# Bank2_I_O.net
KiCad netlist of a schematic drawn in Altium Designer
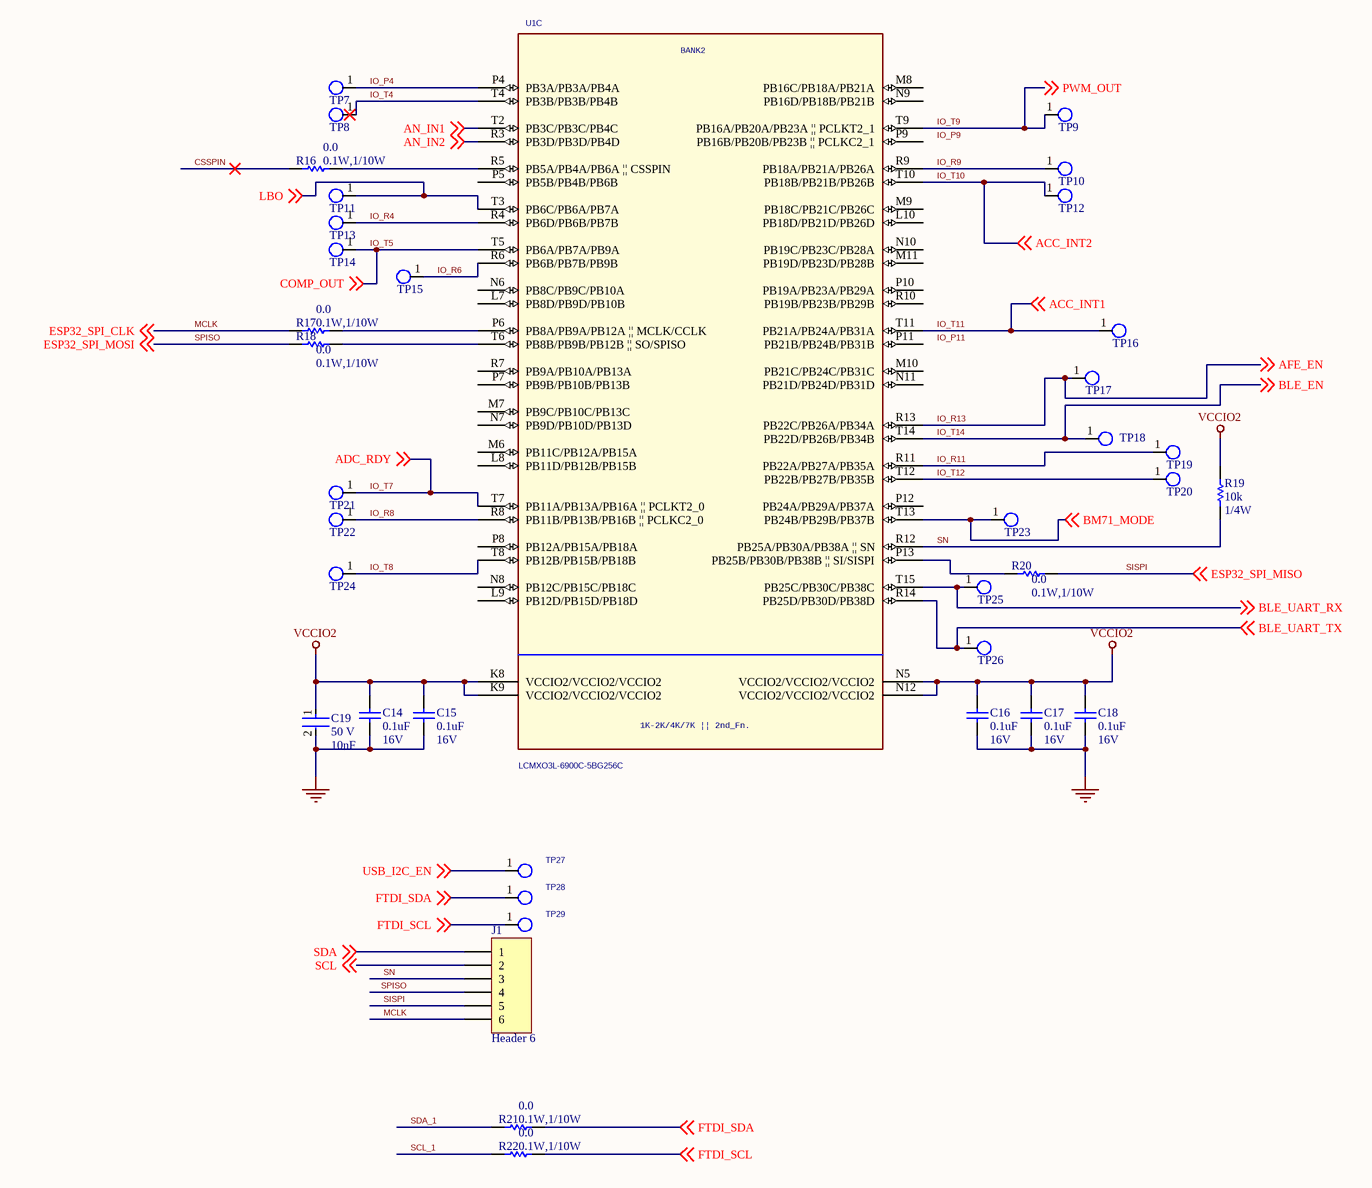
[diagram p0: Bank2_I_O.SchDoc]

(export (version "E")
  (design (tool "Eeschema 10.0.6"))
  (components
    (comp (ref "C14")
      (value "0.1uF")
      (footprint "CAPC1608X87X35ML15T15")
      (description "Ceramic Capacitor 0.1uF 16V +-10% X7R0603")
      (fields
        (field (name "PART NUMBER") "C0603C104M4RACTU")
        (field (name "MANUFACTURER") "Kemet")
        (field (name "VOLTAGE") "16V")
      )
      (libsource (lib "Altium Content Vault") (part "CAP"))
    )
    (comp (ref "C15")
      (value "0.1uF")
      (footprint "CAPC1608X87X35ML15T15")
      (description "Ceramic Capacitor 0.1uF 16V +-10% X7R0603")
      (fields
        (field (name "PART NUMBER") "C0603C104M4RACTU")
        (field (name "MANUFACTURER") "Kemet")
        (field (name "VOLTAGE") "16V")
      )
      (libsource (lib "Altium Content Vault") (part "CAP"))
    )
    (comp (ref "C16")
      (value "0.1uF")
      (footprint "CAPC1608X87X35ML15T15")
      (description "Ceramic Capacitor 0.1uF 16V +-10% X7R0603")
      (fields
        (field (name "PART NUMBER") "C0603C104M4RACTU")
        (field (name "MANUFACTURER") "Kemet")
        (field (name "VOLTAGE") "16V")
      )
      (libsource (lib "Altium Content Vault") (part "CAP"))
    )
    (comp (ref "C17")
      (value "0.1uF")
      (footprint "CAPC1608X87X35ML15T15")
      (description "Ceramic Capacitor 0.1uF 16V +-10% X7R0603")
      (fields
        (field (name "PART NUMBER") "C0603C104M4RACTU")
        (field (name "MANUFACTURER") "Kemet")
        (field (name "VOLTAGE") "16V")
      )
      (libsource (lib "Altium Content Vault") (part "CAP"))
    )
    (comp (ref "C18")
      (value "0.1uF")
      (footprint "CAPC1608X87X35ML15T15")
      (description "Ceramic Capacitor 0.1uF 16V +-10% X7R0603")
      (fields
        (field (name "PART NUMBER") "C0603C104M4RACTU")
        (field (name "MANUFACTURER") "Kemet")
        (field (name "VOLTAGE") "16V")
      )
      (libsource (lib "Altium Content Vault") (part "CAP"))
    )
    (comp (ref "C19")
      (value "10nF")
      (footprint "FP-C0805C-DN-MFG")
      (description "CAP CER 10000PF 50V X7R 0805")
      (fields
        (field (name "VOLTAGE") "50 V")
        (field (name "PART NUMBER") "C0805C103K5RACAUTO")
        (field (name "MANUFACTURER") "KEMET")
      )
      (libsource (lib "Altium Content Vault") (part "b4654b650e69147ec39a6b967a45e02"))
    )
    (comp (ref "J1")
      (value "Header 6")
      (footprint "HDR1X6")
      (description "Header, 6-Pin")
      (fields (field (name "PUBLISHER") "Altium Limited"))
      (libsource (lib "Miscellaneous Connectors") (part "Header 6"))
    )
    (comp (ref "R16")
      (value "0.0")
      (footprint "RESC1608X55X35LL10T10")
      (description "Chip Resistor, 0 Ohm, +/- 5%, 0.1 W, -55 to 155 degC, 0603 (1608 Metric), RoHS, Tape and Reel")
      (fields
        (field (name "POWER") "0.1W,1/10W")
        (field (name "MANUFACTURER") "Samsung-Electro-Mechanics-America,-Inc.")
        (field (name "TOLERANCE") "Jumper")
      )
      (libsource (lib "Altium Content Vault") (part "RES-2"))
    )
    (comp (ref "R17")
      (value "0.0")
      (footprint "RESC1608X55X35LL10T10")
      (description "Chip Resistor, 0 Ohm, +/- 5%, 0.1 W, -55 to 155 degC, 0603 (1608 Metric), RoHS, Tape and Reel")
      (fields
        (field (name "POWER") "0.1W,1/10W")
        (field (name "MANUFACTURER") "Samsung-Electro-Mechanics-America,-Inc.")
        (field (name "TOLERANCE") "Jumper")
      )
      (libsource (lib "Altium Content Vault") (part "RES-2"))
    )
    (comp (ref "R18")
      (value "0.0")
      (footprint "RESC1608X55X35LL10T10")
      (description "Chip Resistor, 0 Ohm, +/- 5%, 0.1 W, -55 to 155 degC, 0603 (1608 Metric), RoHS, Tape and Reel")
      (fields
        (field (name "POWER") "0.1W,1/10W")
        (field (name "MANUFACTURER") "Samsung-Electro-Mechanics-America,-Inc.")
        (field (name "TOLERANCE") "Jumper")
      )
      (libsource (lib "Altium Content Vault") (part "RES-2"))
    )
    (comp (ref "R19")
      (value "10k")
      (footprint "RESC3216X70X50NL05T20")
      (description "Res Thick Film 1206 10k Ohms 5% 1/4W")
      (fields
        (field (name "PART NUMBER") "ERJ-8GEYJ103V")
        (field (name "MANUFACTURER") "Panasonic")
        (field (name "POWER") "1/4W")
      )
      (libsource (lib "Altium Content Vault") (part "RES"))
    )
    (comp (ref "R20")
      (value "0.0")
      (footprint "RESC1608X55X35LL10T10")
      (description "Chip Resistor, 0 Ohm, +/- 5%, 0.1 W, -55 to 155 degC, 0603 (1608 Metric), RoHS, Tape and Reel")
      (fields
        (field (name "POWER") "0.1W,1/10W")
        (field (name "MANUFACTURER") "Samsung-Electro-Mechanics-America,-Inc.")
        (field (name "TOLERANCE") "Jumper")
      )
      (libsource (lib "Altium Content Vault") (part "RES-2"))
    )
    (comp (ref "R21")
      (value "0.0")
      (footprint "RESC1608X55X35LL10T10")
      (description "Chip Resistor, 0 Ohm, +/- 5%, 0.1 W, -55 to 155 degC, 0603 (1608 Metric), RoHS, Tape and Reel")
      (fields
        (field (name "POWER") "0.1W,1/10W")
        (field (name "MANUFACTURER") "Samsung-Electro-Mechanics-America,-Inc.")
        (field (name "TOLERANCE") "Jumper")
      )
      (libsource (lib "Altium Content Vault") (part "RES-2"))
    )
    (comp (ref "R22")
      (value "0.0")
      (footprint "RESC1608X55X35LL10T10")
      (description "Chip Resistor, 0 Ohm, +/- 5%, 0.1 W, -55 to 155 degC, 0603 (1608 Metric), RoHS, Tape and Reel")
      (fields
        (field (name "POWER") "0.1W,1/10W")
        (field (name "MANUFACTURER") "Samsung-Electro-Mechanics-America,-Inc.")
        (field (name "TOLERANCE") "Jumper")
      )
      (libsource (lib "Altium Content Vault") (part "RES-2"))
    )
    (comp (ref "TP7")
      (value "Test_Point_SMD")
      (footprint "Test_Point_SMD")
      (libsource (lib "Edson") (part "Test_Point_SMD"))
    )
    (comp (ref "TP8")
      (value "Test_Point_SMD")
      (footprint "Test_Point_SMD")
      (libsource (lib "Edson") (part "Test_Point_SMD"))
    )
    (comp (ref "TP9")
      (value "Test_Point_SMD")
      (footprint "Test_Point_SMD")
      (libsource (lib "Edson") (part "Test_Point_SMD"))
    )
    (comp (ref "TP10")
      (value "Test_Point_SMD")
      (footprint "Test_Point_SMD")
      (libsource (lib "Edson") (part "Test_Point_SMD"))
    )
    (comp (ref "TP11")
      (value "Test_Point_SMD")
      (footprint "Test_Point_SMD")
      (libsource (lib "Edson") (part "Test_Point_SMD"))
    )
    (comp (ref "TP12")
      (value "Test_Point_SMD")
      (footprint "Test_Point_SMD")
      (libsource (lib "Edson") (part "Test_Point_SMD"))
    )
    (comp (ref "TP13")
      (value "Test_Point_SMD")
      (footprint "Test_Point_SMD")
      (libsource (lib "Edson") (part "Test_Point_SMD"))
    )
    (comp (ref "TP14")
      (value "Test_Point_SMD")
      (footprint "Test_Point_SMD")
      (libsource (lib "Edson") (part "Test_Point_SMD"))
    )
    (comp (ref "TP15")
      (value "Test_Point_SMD")
      (footprint "Test_Point_SMD")
      (libsource (lib "Edson") (part "Test_Point_SMD"))
    )
    (comp (ref "TP16")
      (value "Test_Point_SMD")
      (footprint "Test_Point_SMD")
      (libsource (lib "Edson") (part "Test_Point_SMD"))
    )
    (comp (ref "TP17")
      (value "Test_Point_SMD")
      (footprint "Test_Point_SMD")
      (libsource (lib "Edson") (part "Test_Point_SMD"))
    )
    (comp (ref "TP18")
      (value "Test_Point_SMD")
      (footprint "Test_Point_SMD")
      (libsource (lib "Edson") (part "Test_Point_SMD"))
    )
    (comp (ref "TP19")
      (value "Test_Point_SMD")
      (footprint "Test_Point_SMD")
      (libsource (lib "Edson") (part "Test_Point_SMD"))
    )
    (comp (ref "TP20")
      (value "Test_Point_SMD")
      (footprint "Test_Point_SMD")
      (libsource (lib "Edson") (part "Test_Point_SMD"))
    )
    (comp (ref "TP21")
      (value "Test_Point_SMD")
      (footprint "Test_Point_SMD")
      (libsource (lib "Edson") (part "Test_Point_SMD"))
    )
    (comp (ref "TP22")
      (value "Test_Point_SMD")
      (footprint "Test_Point_SMD")
      (libsource (lib "Edson") (part "Test_Point_SMD"))
    )
    (comp (ref "TP23")
      (value "Test_Point_SMD")
      (footprint "Test_Point_SMD")
      (libsource (lib "Edson") (part "Test_Point_SMD"))
    )
    (comp (ref "TP24")
      (value "Test_Point_SMD")
      (footprint "Test_Point_SMD")
      (libsource (lib "Edson") (part "Test_Point_SMD"))
    )
    (comp (ref "TP25")
      (value "Test_Point_SMD")
      (footprint "Test_Point_SMD")
      (libsource (lib "Edson") (part "Test_Point_SMD"))
    )
    (comp (ref "TP26")
      (value "Test_Point_SMD")
      (footprint "Test_Point_SMD")
      (libsource (lib "Edson") (part "Test_Point_SMD"))
    )
    (comp (ref "TP27")
      (value "tp_s_40_63")
      (footprint "tp_s_40_63")
      (description "Square test point, 40mil inner diameter, 63mil outer diameter")
      (libsource (lib "*") (part "TP_S_40_63"))
    )
    (comp (ref "TP28")
      (value "tp_s_40_63")
      (footprint "tp_s_40_63")
      (description "Square test point, 40mil inner diameter, 63mil outer diameter")
      (libsource (lib "*") (part "TP_S_40_63"))
    )
    (comp (ref "TP29")
      (value "tp_s_40_63")
      (footprint "tp_s_40_63")
      (description "Square test point, 40mil inner diameter, 63mil outer diameter")
      (libsource (lib "*") (part "TP_S_40_63"))
    )
    (comp (ref "U1")
      (value "LCMXO3L-6900C-5BG256C")
      (footprint "BGA256C80P16X16_1400X1400X170")
      (description "IC FPGA 6864LUTS 256BGA")
      (fields (field (name "MANUFACTURER") "Lattice semi"))
      (libsource (lib "*") (part "LCMXO3L-1K/2K/4K/7K-BG256"))
    )
  )
  (nets
    (net (code "1") (name "/CSSPIN") (class "Default")
      (node (ref "R16") (pin "1") (pinfunction "1_1") (pintype "passive"))
    )
    (net (code "2") (name "/IO_P4") (class "Default")
      (node (ref "TP7") (pin "1") (pinfunction "TP_1") (pintype "passive"))
      (node (ref "U1") (pin "P4") (pinfunction "PB3A/PB3A/PB4A_P4") (pintype "bidirectional"))
    )
    (net (code "5") (name "/IO_R4") (class "Default")
      (node (ref "TP13") (pin "1") (pinfunction "TP_1") (pintype "passive"))
      (node (ref "U1") (pin "R4") (pinfunction "PB6D/PB6B/PB7B_R4") (pintype "bidirectional"))
    )
    (net (code "6") (name "/IO_R6") (class "Default")
      (node (ref "TP15") (pin "1") (pinfunction "TP_1") (pintype "passive"))
      (node (ref "U1") (pin "R6") (pinfunction "PB6B/PB7B/PB9B_R6") (pintype "bidirectional"))
    )
    (net (code "7") (name "/IO_R8") (class "Default")
      (node (ref "TP22") (pin "1") (pinfunction "TP_1") (pintype "passive"))
      (node (ref "U1") (pin "R8") (pinfunction "PB11B/PB13B/PB16B_Ζ_PCLKC2_0_R8") (pintype "bidirectional"))
    )
    (net (code "8") (name "/IO_R9") (class "Default")
      (node (ref "TP10") (pin "1") (pinfunction "TP_1") (pintype "passive"))
      (node (ref "U1") (pin "R9") (pinfunction "PB18A/PB21A/PB26A_R9") (pintype "bidirectional"))
    )
    (net (code "9") (name "/IO_R11") (class "Default")
      (node (ref "TP19") (pin "1") (pinfunction "TP_1") (pintype "passive"))
      (node (ref "U1") (pin "R11") (pinfunction "PB22A/PB27A/PB35A_R11") (pintype "bidirectional"))
    )
    (net (code "10") (name "/IO_T4") (class "Default")
      (node (ref "TP8") (pin "1") (pinfunction "TP_1") (pintype "passive"))
      (node (ref "U1") (pin "T4") (pinfunction "PB3B/PB3B/PB4B_T4") (pintype "bidirectional"))
    )
    (net (code "11") (name "/IO_T8") (class "Default")
      (node (ref "TP24") (pin "1") (pinfunction "TP_1") (pintype "passive"))
      (node (ref "U1") (pin "T8") (pinfunction "PB12B/PB15B/PB18B_T8") (pintype "bidirectional"))
    )
    (net (code "12") (name "/IO_T12") (class "Default")
      (node (ref "TP20") (pin "1") (pinfunction "TP_1") (pintype "passive"))
      (node (ref "U1") (pin "T12") (pinfunction "PB22B/PB27B/PB35B_T12") (pintype "bidirectional"))
    )
    (net (code "13") (name "/SCL_1") (class "Default")
      (node (ref "R22") (pin "1") (pinfunction "1_1") (pintype "passive"))
    )
    (net (code "14") (name "/SDA_1") (class "Default")
      (node (ref "R21") (pin "1") (pinfunction "1_1") (pintype "passive"))
    )
    (net (code "15") (name "/SN") (class "Default")
      (node (ref "J1") (pin "3") (pinfunction "3_3") (pintype "passive"))
      (node (ref "R19") (pin "2") (pinfunction "2_2") (pintype "passive"))
      (node (ref "U1") (pin "R12") (pinfunction "PB25A/PB30A/PB38A_Ζ_SN_R12") (pintype "bidirectional"))
    )
    (net (code "16") (name "ACC_INT1") (class "Default")
      (node (ref "TP16") (pin "1") (pinfunction "TP_1") (pintype "passive"))
      (node (ref "U1") (pin "T11") (pinfunction "PB21A/PB24A/PB31A_T11") (pintype "bidirectional"))
    )
    (net (code "17") (name "ACC_INT2") (class "Default")
      (node (ref "TP12") (pin "1") (pinfunction "TP_1") (pintype "passive"))
      (node (ref "U1") (pin "T10") (pinfunction "PB18B/PB21B/PB26B_T10") (pintype "bidirectional"))
    )
    (net (code "18") (name "ADC_RDY") (class "Default")
      (node (ref "TP21") (pin "1") (pinfunction "TP_1") (pintype "passive"))
      (node (ref "U1") (pin "T7") (pinfunction "PB11A/PB13A/PB16A_Ζ_PCLKT2_0_T7") (pintype "bidirectional"))
    )
    (net (code "19") (name "AFE_EN") (class "Default")
      (node (ref "TP17") (pin "1") (pinfunction "TP_1") (pintype "passive"))
      (node (ref "U1") (pin "R13") (pinfunction "PB22C/PB26A/PB34A_R13") (pintype "bidirectional"))
    )
    (net (code "20") (name "AN_IN1") (class "Default")
      (node (ref "U1") (pin "T2") (pinfunction "PB3C/PB3C/PB4C_T2") (pintype "bidirectional"))
    )
    (net (code "21") (name "AN_IN2") (class "Default")
      (node (ref "U1") (pin "R3") (pinfunction "PB3D/PB3D/PB4D_R3") (pintype "bidirectional"))
    )
    (net (code "22") (name "BLE_EN") (class "Default")
      (node (ref "TP18") (pin "1") (pinfunction "TP_1") (pintype "passive"))
      (node (ref "U1") (pin "T14") (pinfunction "PB22D/PB26B/PB34B_T14") (pintype "bidirectional"))
    )
    (net (code "23") (name "BLE_UART_RX") (class "Default")
      (node (ref "TP25") (pin "1") (pinfunction "TP_1") (pintype "passive"))
      (node (ref "U1") (pin "T15") (pinfunction "PB25C/PB30C/PB38C_T15") (pintype "bidirectional"))
    )
    (net (code "24") (name "BLE_UART_TX") (class "Default")
      (node (ref "TP26") (pin "1") (pinfunction "TP_1") (pintype "passive"))
      (node (ref "U1") (pin "R14") (pinfunction "PB25D/PB30D/PB38D_R14") (pintype "bidirectional"))
    )
    (net (code "25") (name "BM71_MODE") (class "Default")
      (node (ref "TP23") (pin "1") (pinfunction "TP_1") (pintype "passive"))
      (node (ref "U1") (pin "T13") (pinfunction "PB24B/PB29B/PB37B_T13") (pintype "bidirectional"))
    )
    (net (code "26") (name "COMP_OUT") (class "Default")
      (node (ref "TP14") (pin "1") (pinfunction "TP_1") (pintype "passive"))
      (node (ref "U1") (pin "T5") (pinfunction "PB6A/PB7A/PB9A_T5") (pintype "bidirectional"))
    )
    (net (code "27") (name "ESP32_SPI_CLK") (class "Default")
      (node (ref "J1") (pin "6") (pinfunction "6_6") (pintype "passive"))
      (node (ref "R17") (pin "1") (pinfunction "1_1") (pintype "passive"))
    )
    (net (code "28") (name "ESP32_SPI_MISO") (class "Default")
      (node (ref "J1") (pin "5") (pinfunction "5_5") (pintype "passive"))
      (node (ref "R20") (pin "2") (pinfunction "2_2") (pintype "passive"))
    )
    (net (code "29") (name "ESP32_SPI_MOSI") (class "Default")
      (node (ref "J1") (pin "4") (pinfunction "4_4") (pintype "passive"))
      (node (ref "R18") (pin "1") (pinfunction "1_1") (pintype "passive"))
    )
    (net (code "30") (name "FTDI_SCL") (class "Default")
      (node (ref "R22") (pin "2") (pinfunction "2_2") (pintype "passive"))
      (node (ref "TP29") (pin "1") (pinfunction "TP_1") (pintype "passive"))
    )
    (net (code "31") (name "FTDI_SDA") (class "Default")
      (node (ref "R21") (pin "2") (pinfunction "2_2") (pintype "passive"))
      (node (ref "TP28") (pin "1") (pinfunction "TP_1") (pintype "passive"))
    )
    (net (code "32") (name "GND") (class "Default")
      (node (ref "C14") (pin "2") (pinfunction "2_2") (pintype "passive"))
      (node (ref "C15") (pin "2") (pinfunction "2_2") (pintype "passive"))
      (node (ref "C16") (pin "2") (pinfunction "2_2") (pintype "passive"))
      (node (ref "C17") (pin "2") (pinfunction "2_2") (pintype "passive"))
      (node (ref "C18") (pin "2") (pinfunction "2_2") (pintype "passive"))
      (node (ref "C19") (pin "2") (pinfunction "2_2") (pintype "passive"))
    )
    (net (code "33") (name "LBO") (class "Default")
      (node (ref "TP11") (pin "1") (pinfunction "TP_1") (pintype "passive"))
      (node (ref "U1") (pin "T3") (pinfunction "PB6C/PB6A/PB7A_T3") (pintype "bidirectional"))
    )
    (net (code "34") (name "Net-(U1C-PB5A{slash}PB4A{slash}PB6A_Ζ_CSSPIN)") (class "Default")
      (node (ref "R16") (pin "2") (pinfunction "2_2") (pintype "passive"))
      (node (ref "U1") (pin "R5") (pinfunction "PB5A/PB4A/PB6A_Ζ_CSSPIN_R5") (pintype "bidirectional"))
    )
    (net (code "35") (name "Net-(U1C-PB8A{slash}PB9A{slash}PB12A_Ζ_MCLK{slash}CCLK)") (class "Default")
      (node (ref "R17") (pin "2") (pinfunction "2_2") (pintype "passive"))
      (node (ref "U1") (pin "P6") (pinfunction "PB8A/PB9A/PB12A_Ζ_MCLK/CCLK_P6") (pintype "bidirectional"))
    )
    (net (code "36") (name "Net-(U1C-PB8B{slash}PB9B{slash}PB12B_Ζ_SO{slash}SPISO)") (class "Default")
      (node (ref "R18") (pin "2") (pinfunction "2_2") (pintype "passive"))
      (node (ref "U1") (pin "T6") (pinfunction "PB8B/PB9B/PB12B_Ζ_SO/SPISO_T6") (pintype "bidirectional"))
    )
    (net (code "37") (name "Net-(U1C-PB25B{slash}PB30B{slash}PB38B_Ζ_SI{slash}SISPI)") (class "Default")
      (node (ref "R20") (pin "1") (pinfunction "1_1") (pintype "passive"))
      (node (ref "U1") (pin "P13") (pinfunction "PB25B/PB30B/PB38B_Ζ_SI/SISPI_P13") (pintype "bidirectional"))
    )
    (net (code "38") (name "PWM_OUT") (class "Default")
      (node (ref "TP9") (pin "1") (pinfunction "TP_1") (pintype "passive"))
      (node (ref "U1") (pin "T9") (pinfunction "PB16A/PB20A/PB23A_Ζ_PCLKT2_1_T9") (pintype "bidirectional"))
    )
    (net (code "39") (name "SCL") (class "Default")
      (node (ref "J1") (pin "2") (pinfunction "2_2") (pintype "passive"))
    )
    (net (code "40") (name "SDA") (class "Default")
      (node (ref "J1") (pin "1") (pinfunction "1_1") (pintype "passive"))
    )
    (net (code "41") (name "USB_I2C_EN") (class "Default")
      (node (ref "TP27") (pin "1") (pinfunction "TP_1") (pintype "passive"))
    )
    (net (code "42") (name "VCCIO2") (class "Default")
      (node (ref "C14") (pin "1") (pinfunction "1_1") (pintype "passive"))
      (node (ref "C15") (pin "1") (pinfunction "1_1") (pintype "passive"))
      (node (ref "C16") (pin "1") (pinfunction "1_1") (pintype "passive"))
      (node (ref "C17") (pin "1") (pinfunction "1_1") (pintype "passive"))
      (node (ref "C18") (pin "1") (pinfunction "1_1") (pintype "passive"))
      (node (ref "C19") (pin "1") (pinfunction "1_1") (pintype "passive"))
      (node (ref "R19") (pin "1") (pinfunction "1_1") (pintype "passive"))
      (node (ref "U1") (pin "K8") (pinfunction "VCCIO2/VCCIO2/VCCIO2_K8") (pintype "power_in"))
      (node (ref "U1") (pin "K9") (pinfunction "VCCIO2/VCCIO2/VCCIO2_K9") (pintype "power_in"))
      (node (ref "U1") (pin "N12") (pinfunction "VCCIO2/VCCIO2/VCCIO2_N12") (pintype "power_in"))
      (node (ref "U1") (pin "N5") (pinfunction "VCCIO2/VCCIO2/VCCIO2_N5") (pintype "power_in"))
    )
    (net (code "43") (name "unconnected-(U1C-PB5B{slash}PB4B{slash}PB6B-PadP5)") (class "Default")
      (node (ref "U1") (pin "P5") (pinfunction "PB5B/PB4B/PB6B_P5") (pintype "bidirectional"))
    )
    (net (code "44") (name "unconnected-(U1C-PB8C{slash}PB9C{slash}PB10A-PadN6)") (class "Default")
      (node (ref "U1") (pin "N6") (pinfunction "PB8C/PB9C/PB10A_N6") (pintype "bidirectional"))
    )
    (net (code "45") (name "unconnected-(U1C-PB8D{slash}PB9D{slash}PB10B-PadL7)") (class "Default")
      (node (ref "U1") (pin "L7") (pinfunction "PB8D/PB9D/PB10B_L7") (pintype "bidirectional"))
    )
    (net (code "46") (name "unconnected-(U1C-PB9A{slash}PB10A{slash}PB13A-PadR7)") (class "Default")
      (node (ref "U1") (pin "R7") (pinfunction "PB9A/PB10A/PB13A_R7") (pintype "bidirectional"))
    )
    (net (code "47") (name "unconnected-(U1C-PB9B{slash}PB10B{slash}PB13B-PadP7)") (class "Default")
      (node (ref "U1") (pin "P7") (pinfunction "PB9B/PB10B/PB13B_P7") (pintype "bidirectional"))
    )
    (net (code "48") (name "unconnected-(U1C-PB9C{slash}PB10C{slash}PB13C-PadM7)") (class "Default")
      (node (ref "U1") (pin "M7") (pinfunction "PB9C/PB10C/PB13C_M7") (pintype "bidirectional"))
    )
    (net (code "49") (name "unconnected-(U1C-PB9D{slash}PB10D{slash}PB13D-PadN7)") (class "Default")
      (node (ref "U1") (pin "N7") (pinfunction "PB9D/PB10D/PB13D_N7") (pintype "bidirectional"))
    )
    (net (code "50") (name "unconnected-(U1C-PB11C{slash}PB12A{slash}PB15A-PadM6)") (class "Default")
      (node (ref "U1") (pin "M6") (pinfunction "PB11C/PB12A/PB15A_M6") (pintype "bidirectional"))
    )
    (net (code "51") (name "unconnected-(U1C-PB11D{slash}PB12B{slash}PB15B-PadL8)") (class "Default")
      (node (ref "U1") (pin "L8") (pinfunction "PB11D/PB12B/PB15B_L8") (pintype "bidirectional"))
    )
    (net (code "52") (name "unconnected-(U1C-PB12A{slash}PB15A{slash}PB18A-PadP8)") (class "Default")
      (node (ref "U1") (pin "P8") (pinfunction "PB12A/PB15A/PB18A_P8") (pintype "bidirectional"))
    )
    (net (code "53") (name "unconnected-(U1C-PB12C{slash}PB15C{slash}PB18C-PadN8)") (class "Default")
      (node (ref "U1") (pin "N8") (pinfunction "PB12C/PB15C/PB18C_N8") (pintype "bidirectional"))
    )
    (net (code "54") (name "unconnected-(U1C-PB12D{slash}PB15D{slash}PB18D-PadL9)") (class "Default")
      (node (ref "U1") (pin "L9") (pinfunction "PB12D/PB15D/PB18D_L9") (pintype "bidirectional"))
    )
    (net (code "55") (name "unconnected-(U1C-PB16B{slash}PB20B{slash}PB23B_Ζ_PCLKC2_1-PadP9)") (class "Default")
      (node (ref "U1") (pin "P9") (pinfunction "PB16B/PB20B/PB23B_Ζ_PCLKC2_1_P9") (pintype "bidirectional"))
    )
    (net (code "56") (name "unconnected-(U1C-PB16C{slash}PB18A{slash}PB21A-PadM8)") (class "Default")
      (node (ref "U1") (pin "M8") (pinfunction "PB16C/PB18A/PB21A_M8") (pintype "bidirectional"))
    )
    (net (code "57") (name "unconnected-(U1C-PB16D{slash}PB18B{slash}PB21B-PadN9)") (class "Default")
      (node (ref "U1") (pin "N9") (pinfunction "PB16D/PB18B/PB21B_N9") (pintype "bidirectional"))
    )
    (net (code "58") (name "unconnected-(U1C-PB18C{slash}PB21C{slash}PB26C-PadM9)") (class "Default")
      (node (ref "U1") (pin "M9") (pinfunction "PB18C/PB21C/PB26C_M9") (pintype "bidirectional"))
    )
    (net (code "59") (name "unconnected-(U1C-PB18D{slash}PB21D{slash}PB26D-PadL10)") (class "Default")
      (node (ref "U1") (pin "L10") (pinfunction "PB18D/PB21D/PB26D_L10") (pintype "bidirectional"))
    )
    (net (code "60") (name "unconnected-(U1C-PB19A{slash}PB23A{slash}PB29A-PadP10)") (class "Default")
      (node (ref "U1") (pin "P10") (pinfunction "PB19A/PB23A/PB29A_P10") (pintype "bidirectional"))
    )
    (net (code "61") (name "unconnected-(U1C-PB19B{slash}PB23B{slash}PB29B-PadR10)") (class "Default")
      (node (ref "U1") (pin "R10") (pinfunction "PB19B/PB23B/PB29B_R10") (pintype "bidirectional"))
    )
    (net (code "62") (name "unconnected-(U1C-PB19C{slash}PB23C{slash}PB28A-PadN10)") (class "Default")
      (node (ref "U1") (pin "N10") (pinfunction "PB19C/PB23C/PB28A_N10") (pintype "bidirectional"))
    )
    (net (code "63") (name "unconnected-(U1C-PB19D{slash}PB23D{slash}PB28B-PadM11)") (class "Default")
      (node (ref "U1") (pin "M11") (pinfunction "PB19D/PB23D/PB28B_M11") (pintype "bidirectional"))
    )
    (net (code "64") (name "unconnected-(U1C-PB21B{slash}PB24B{slash}PB31B-PadP11)") (class "Default")
      (node (ref "U1") (pin "P11") (pinfunction "PB21B/PB24B/PB31B_P11") (pintype "bidirectional"))
    )
    (net (code "65") (name "unconnected-(U1C-PB21C{slash}PB24C{slash}PB31C-PadM10)") (class "Default")
      (node (ref "U1") (pin "M10") (pinfunction "PB21C/PB24C/PB31C_M10") (pintype "bidirectional"))
    )
    (net (code "66") (name "unconnected-(U1C-PB21D{slash}PB24D{slash}PB31D-PadN11)") (class "Default")
      (node (ref "U1") (pin "N11") (pinfunction "PB21D/PB24D/PB31D_N11") (pintype "bidirectional"))
    )
    (net (code "67") (name "unconnected-(U1C-PB24A{slash}PB29A{slash}PB37A-PadP12)") (class "Default")
      (node (ref "U1") (pin "P12") (pinfunction "PB24A/PB29A/PB37A_P12") (pintype "bidirectional"))
    )
  )
)
